# IF_AMP.net
KiCad netlist of a schematic drawn in Altium Designer
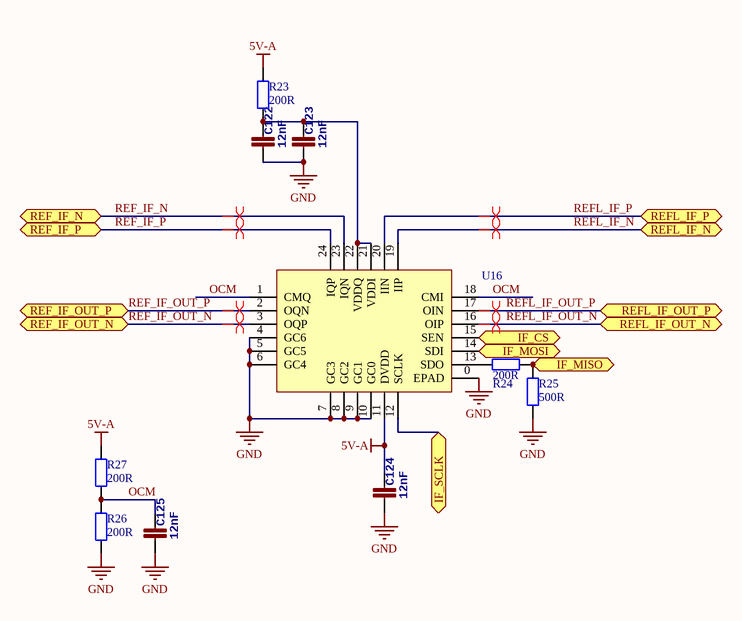
[diagram p0: IF_AMP.SchDoc]

(export (version "E")
  (design (tool "Eeschema 10.0.6"))
  (components
    (comp (ref "C122")
      (value "12nF")
      (footprint "0402")
      (description "<b>Capacitor</b>\nStandard 0603 ceramic capacitor, and 0.1\" leaded capacitor.")
      (fields (field (name "PARTNO") "CC0402ZRY5V7BB104"))
      (libsource (lib "pixhawk2") (part "CAP0402-CAP"))
    )
    (comp (ref "C123")
      (value "12nF")
      (footprint "0402")
      (description "<b>Capacitor</b>\nStandard 0603 ceramic capacitor, and 0.1\" leaded capacitor.")
      (fields (field (name "PARTNO") "CC0402ZRY5V7BB104"))
      (libsource (lib "pixhawk2") (part "CAP0402-CAP"))
    )
    (comp (ref "C124")
      (value "12nF")
      (footprint "0402")
      (description "<b>Capacitor</b>\nStandard 0603 ceramic capacitor, and 0.1\" leaded capacitor.")
      (fields (field (name "PARTNO") "CC0402ZRY5V7BB104"))
      (libsource (lib "pixhawk2") (part "CAP0402-CAP"))
    )
    (comp (ref "C125")
      (value "12nF")
      (footprint "0402")
      (description "<b>Capacitor</b>\nStandard 0603 ceramic capacitor, and 0.1\" leaded capacitor.")
      (fields (field (name "PARTNO") "CC0402ZRY5V7BB104"))
      (libsource (lib "pixhawk2") (part "CAP0402-CAP"))
    )
    (comp (ref "R23")
      (value "200R")
      (footprint "0402")
      (description "Resistor")
      (fields (field (name "PUBLISHER") "Altium Limited"))
      (libsource (lib "") (part "Res2_1"))
    )
    (comp (ref "R24")
      (value "200R")
      (footprint "0402")
      (description "Resistor")
      (fields (field (name "PUBLISHER") "Altium Limited"))
      (libsource (lib "") (part "Res2_2"))
    )
    (comp (ref "R25")
      (value "500R")
      (footprint "0402")
      (description "Resistor")
      (fields (field (name "PUBLISHER") "Altium Limited"))
      (libsource (lib "Miscellaneous Devices") (part "Res2"))
    )
    (comp (ref "R26")
      (value "200R")
      (footprint "0402")
      (description "Resistor")
      (fields (field (name "PUBLISHER") "Altium Limited"))
      (libsource (lib "") (part "Res2_1"))
    )
    (comp (ref "R27")
      (value "200R")
      (footprint "0402")
      (description "Resistor")
      (fields (field (name "PUBLISHER") "Altium Limited"))
      (libsource (lib "") (part "Res2_1"))
    )
    (comp (ref "U16") (value "HMC960") (footprint "HMC960") (libsource (lib "F4SDR") (part "HMC960")))
  )
  (nets
    (net (code "1") (name "/IF_CS") (class "Default")
      (node (ref "U16") (pin "15") (pinfunction "SEN_15") (pintype "passive"))
    )
    (net (code "2") (name "/IF_MISO") (class "Default")
      (node (ref "R24") (pin "2") (pinfunction "2_2") (pintype "passive"))
      (node (ref "R25") (pin "2") (pinfunction "2_2") (pintype "passive"))
    )
    (net (code "3") (name "/IF_MOSI") (class "Default")
      (node (ref "U16") (pin "14") (pinfunction "SDI_14") (pintype "passive"))
    )
    (net (code "4") (name "/IF_SCLK") (class "Default")
      (node (ref "U16") (pin "12") (pinfunction "SCLK_12") (pintype "passive"))
    )
    (net (code "5") (name "/OCM") (class "Default")
      (node (ref "C125") (pin "2") (pinfunction "2_2") (pintype "passive"))
      (node (ref "R26") (pin "1") (pinfunction "1_1") (pintype "passive"))
      (node (ref "R27") (pin "2") (pinfunction "2_2") (pintype "passive"))
      (node (ref "U16") (pin "1") (pinfunction "CMQ_1") (pintype "passive"))
      (node (ref "U16") (pin "18") (pinfunction "CMI_18") (pintype "passive"))
    )
    (net (code "6") (name "/REFL_IF_N") (class "Default")
      (node (ref "U16") (pin "19") (pinfunction "IIP_19") (pintype "passive"))
    )
    (net (code "7") (name "/REFL_IF_OUT_N") (class "Default")
      (node (ref "U16") (pin "16") (pinfunction "OIP_16") (pintype "passive"))
    )
    (net (code "8") (name "/REFL_IF_OUT_P") (class "Default")
      (node (ref "U16") (pin "17") (pinfunction "OIN_17") (pintype "passive"))
    )
    (net (code "9") (name "/REFL_IF_P") (class "Default")
      (node (ref "U16") (pin "20") (pinfunction "IIN_20") (pintype "passive"))
    )
    (net (code "10") (name "/REF_IF_N") (class "Default")
      (node (ref "U16") (pin "23") (pinfunction "IQN_23") (pintype "passive"))
    )
    (net (code "11") (name "/REF_IF_OUT_N") (class "Default")
      (node (ref "U16") (pin "3") (pinfunction "OQP_3") (pintype "passive"))
    )
    (net (code "12") (name "/REF_IF_OUT_P") (class "Default")
      (node (ref "U16") (pin "2") (pinfunction "OQN_2") (pintype "passive"))
    )
    (net (code "13") (name "/REF_IF_P") (class "Default")
      (node (ref "U16") (pin "24") (pinfunction "IQP_24") (pintype "passive"))
    )
    (net (code "14") (name "5V-A") (class "Default")
      (node (ref "C124") (pin "2") (pinfunction "2_2") (pintype "passive"))
      (node (ref "R23") (pin "1") (pinfunction "1_1") (pintype "passive"))
      (node (ref "R27") (pin "1") (pinfunction "1_1") (pintype "passive"))
      (node (ref "U16") (pin "11") (pinfunction "DVDD_11") (pintype "passive"))
    )
    (net (code "15") (name "GND") (class "Default")
      (node (ref "C122") (pin "1") (pinfunction "1_1") (pintype "passive"))
      (node (ref "C123") (pin "1") (pinfunction "1_1") (pintype "passive"))
      (node (ref "C124") (pin "1") (pinfunction "1_1") (pintype "passive"))
      (node (ref "C125") (pin "1") (pinfunction "1_1") (pintype "passive"))
      (node (ref "R25") (pin "1") (pinfunction "1_1") (pintype "passive"))
      (node (ref "R26") (pin "2") (pinfunction "2_2") (pintype "passive"))
      (node (ref "U16") (pin "0") (pinfunction "EPAD_0") (pintype "passive"))
      (node (ref "U16") (pin "10") (pinfunction "GC0_10") (pintype "passive"))
      (node (ref "U16") (pin "4") (pinfunction "GC6_4") (pintype "passive"))
      (node (ref "U16") (pin "5") (pinfunction "GC5_5") (pintype "passive"))
      (node (ref "U16") (pin "6") (pinfunction "GC4_6") (pintype "passive"))
      (node (ref "U16") (pin "7") (pinfunction "GC3_7") (pintype "passive"))
      (node (ref "U16") (pin "8") (pinfunction "GC2_8") (pintype "passive"))
      (node (ref "U16") (pin "9") (pinfunction "GC1_9") (pintype "passive"))
    )
    (net (code "16") (name "Net-(U16-SDO)") (class "Default")
      (node (ref "R24") (pin "1") (pinfunction "1_1") (pintype "passive"))
      (node (ref "U16") (pin "13") (pinfunction "SDO_13") (pintype "passive"))
    )
    (net (code "17") (name "Net-(U16-VDDI)") (class "Default")
      (node (ref "C122") (pin "2") (pinfunction "2_2") (pintype "passive"))
      (node (ref "C123") (pin "2") (pinfunction "2_2") (pintype "passive"))
      (node (ref "R23") (pin "2") (pinfunction "2_2") (pintype "passive"))
      (node (ref "U16") (pin "21") (pinfunction "VDDI_21") (pintype "passive"))
      (node (ref "U16") (pin "22") (pinfunction "VDDQ_22") (pintype "passive"))
    )
  )
)
